# StemsField_motor_V1_0.net
KiCad netlist of a schematic drawn in EAGLE
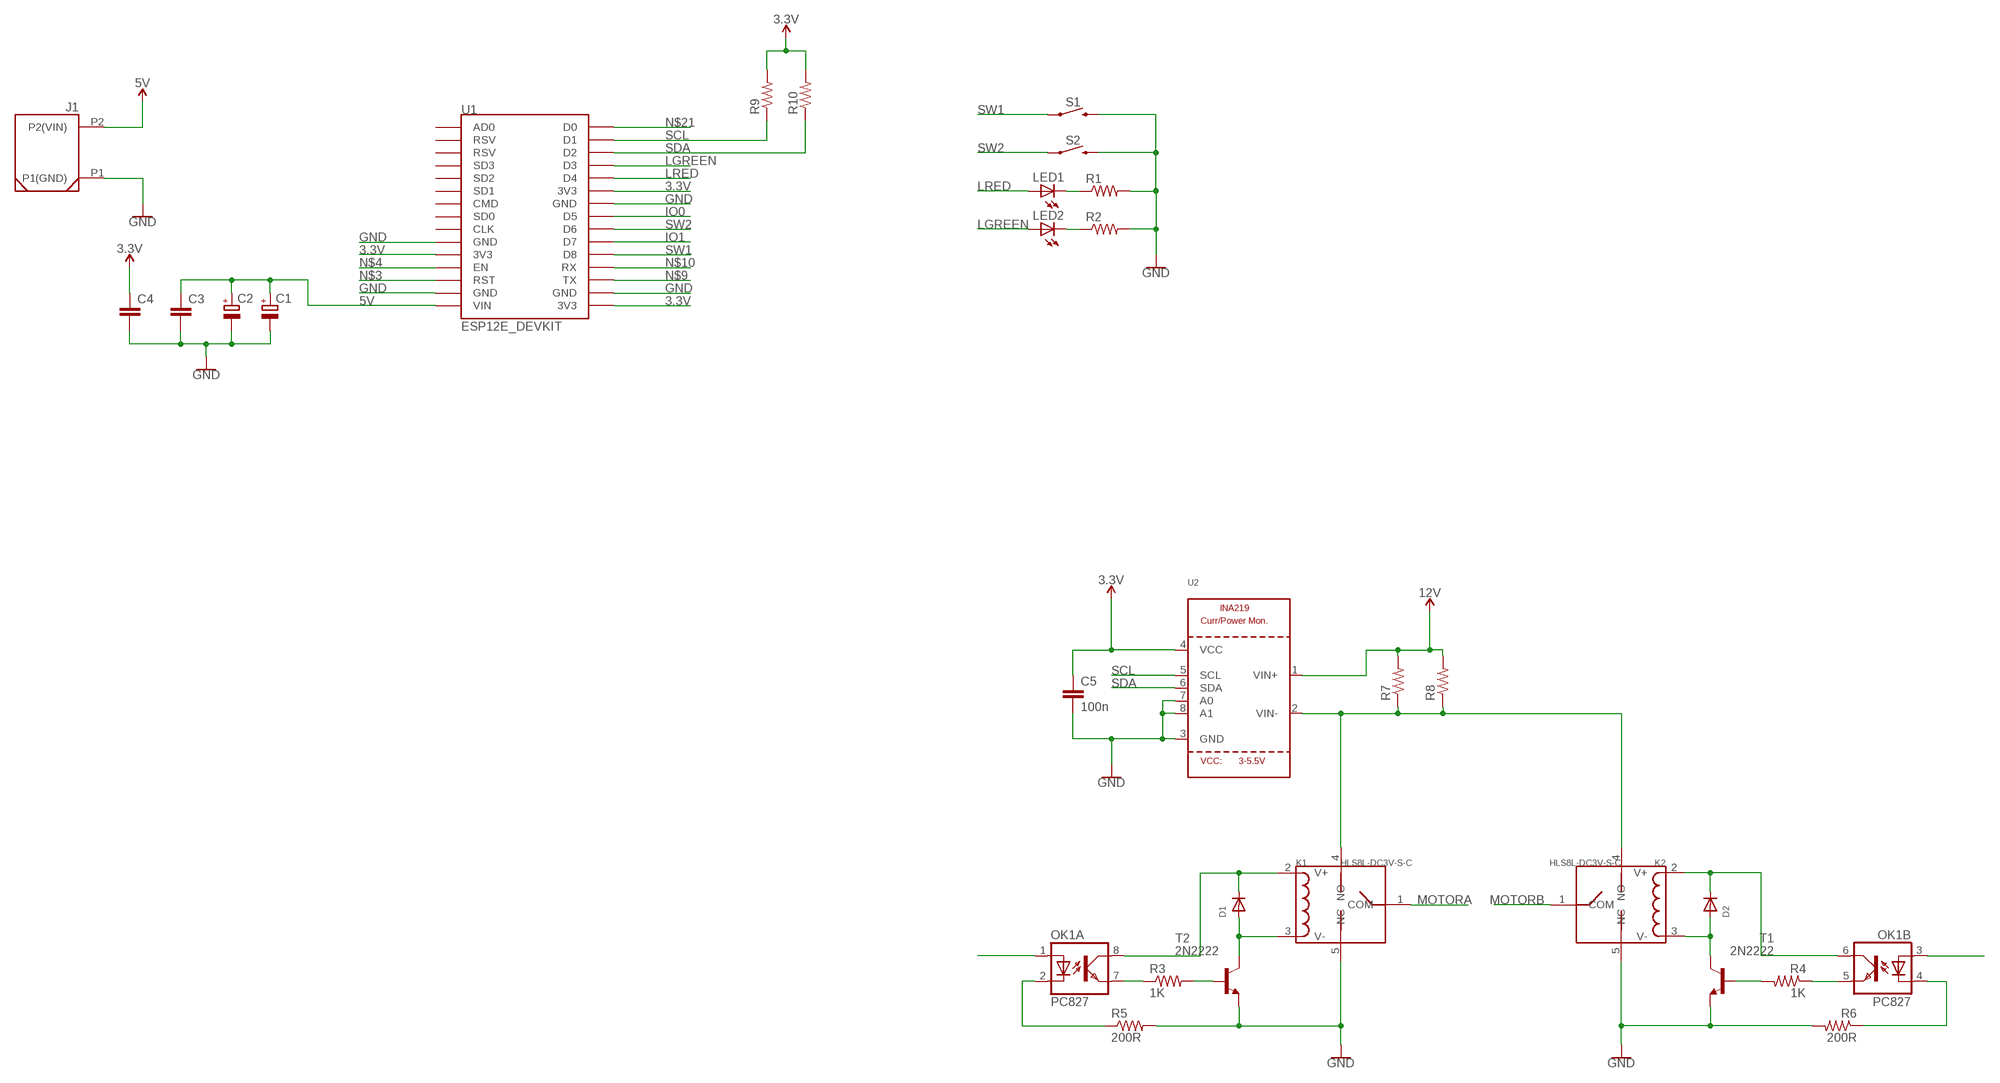
[diagram p0: schematic, sheet 1]

(export (version "E")
  (design (tool "Eeschema 10.0.6"))
  (components
    (comp (ref "C1")
      (value "CPOL-EUE3.5-8")
      (footprint "eagle-import:E3,5-8")
      (libsource (lib "eagle-import") (part "CPOL-EUE3.5-8"))
    )
    (comp (ref "C2")
      (value "CPOL-EUE3.5-8")
      (footprint "eagle-import:E3,5-8")
      (libsource (lib "eagle-import") (part "CPOL-EUE3.5-8"))
    )
    (comp (ref "C3")
      (value "C-EU025-024X044")
      (footprint "eagle-import:C025-024X044")
      (libsource (lib "eagle-import") (part "C-EU025-024X044"))
    )
    (comp (ref "C4")
      (value "C-EU025-024X044")
      (footprint "eagle-import:C025-024X044")
      (libsource (lib "eagle-import") (part "C-EU025-024X044"))
    )
    (comp (ref "C5")
      (value "100n")
      (footprint "eagle-import:C025-024X044")
      (libsource (lib "eagle-import") (part "C-EU025-024X044"))
    )
    (comp (ref "D1")
      (value "DIODEDO-1N4148")
      (footprint "eagle-import:DO-1N4148")
      (libsource (lib "eagle-import") (part "DIODEDO-1N4148"))
    )
    (comp (ref "D2")
      (value "DIODEDO-1N4148")
      (footprint "eagle-import:DO-1N4148")
      (libsource (lib "eagle-import") (part "DIODEDO-1N4148"))
    )
    (comp (ref "J1")
      (value "XT30PWM")
      (footprint "eagle-import:XT30PW-M")
      (libsource (lib "eagle-import") (part "XT30PWM"))
    )
    (comp (ref "K1")
      (value "HLS8L-DC3V-S-C")
      (footprint "eagle-import:REY5-19.0X15.0X15.0MM")
      (libsource (lib "eagle-import") (part "RELAY-HLS8L-DC3V-S-C(5P-19X15MM)"))
    )
    (comp (ref "K2")
      (value "HLS8L-DC3V-S-C")
      (footprint "eagle-import:REY5-19.0X15.0X15.0MM")
      (libsource (lib "eagle-import") (part "RELAY-HLS8L-DC3V-S-C(5P-19X15MM)"))
    )
    (comp (ref "LED1")
      (value "LED3MM")
      (footprint "eagle-import:LED3MM")
      (libsource (lib "eagle-import") (part "LED3MM"))
    )
    (comp (ref "LED2")
      (value "LED3MM")
      (footprint "eagle-import:LED3MM")
      (libsource (lib "eagle-import") (part "LED3MM"))
    )
    (comp (ref "OK1")
      (value "PC827")
      (footprint "eagle-import:DIL08")
      (libsource (lib "eagle-import") (part "PC827"))
    )
    (comp (ref "R1")
      (value "R-US_0204/5")
      (footprint "eagle-import:0204_5")
      (libsource (lib "eagle-import") (part "R-US_0204/5"))
    )
    (comp (ref "R2")
      (value "R-US_0204/5")
      (footprint "eagle-import:0204_5")
      (libsource (lib "eagle-import") (part "R-US_0204/5"))
    )
    (comp (ref "R3")
      (value "1K")
      (footprint "eagle-import:0204_7")
      (libsource (lib "eagle-import") (part "R-US_0204/7"))
    )
    (comp (ref "R4")
      (value "1K")
      (footprint "eagle-import:0204_7")
      (libsource (lib "eagle-import") (part "R-US_0204/7"))
    )
    (comp (ref "R5")
      (value "200R")
      (footprint "eagle-import:0204_7")
      (libsource (lib "eagle-import") (part "R-US_0204/7"))
    )
    (comp (ref "R6")
      (value "200R")
      (footprint "eagle-import:0204_7")
      (libsource (lib "eagle-import") (part "R-US_0204/7"))
    )
    (comp (ref "R7")
      (value "R-US_0204/7")
      (footprint "eagle-import:0204_7")
      (libsource (lib "eagle-import") (part "resistor_348_R-US_0204/7"))
    )
    (comp (ref "R8")
      (value "R-US_R2512")
      (footprint "eagle-import:R2512")
      (libsource (lib "eagle-import") (part "resistor_348_R-US_R2512"))
    )
    (comp (ref "R9")
      (value "R-US_0204/5")
      (footprint "eagle-import:0204_5")
      (libsource (lib "eagle-import") (part "R-US_0204/5"))
    )
    (comp (ref "R10")
      (value "R-US_0204/5")
      (footprint "eagle-import:0204_5")
      (libsource (lib "eagle-import") (part "R-US_0204/5"))
    )
    (comp (ref "S1")
      (value "MOMENTARY-SWITCH-SPST-PTH-6.0MM")
      (footprint "eagle-import:TACTILE_SWITCH_PTH_6.0MM")
      (libsource (lib "eagle-import") (part "MOMENTARY-SWITCH-SPST-PTH-6.0MM"))
    )
    (comp (ref "S2")
      (value "MOMENTARY-SWITCH-SPST-PTH-6.0MM")
      (footprint "eagle-import:TACTILE_SWITCH_PTH_6.0MM")
      (libsource (lib "eagle-import") (part "MOMENTARY-SWITCH-SPST-PTH-6.0MM"))
    )
    (comp (ref "T1")
      (value "2N2222")
      (footprint "eagle-import:TO92-EBC-OVAL")
      (libsource (lib "eagle-import") (part "2N2222"))
    )
    (comp (ref "T2")
      (value "2N2222")
      (footprint "eagle-import:TO92-EBC-OVAL")
      (libsource (lib "eagle-import") (part "2N2222"))
    )
    (comp (ref "U1")
      (value "ESP12E_DEVKIT")
      (footprint "eagle-import:ESP12E_DEVKIT")
      (libsource (lib "eagle-import") (part "ESP12E_DEVKIT"))
    )
    (comp (ref "U2")
      (value "INA219")
      (footprint "eagle-import:SOT23-8")
      (libsource (lib "eagle-import") (part "INA219"))
    )
  )
  (nets
    (net (code "1") (name "/IO0") (class "Default")
      (node (ref "U1") (pin "D5") (pinfunction "D5_D5") (pintype "bidirectional"))
    )
    (net (code "2") (name "/IO1") (class "Default")
      (node (ref "U1") (pin "D7") (pinfunction "D7_D7") (pintype "bidirectional"))
    )
    (net (code "3") (name "/LGREEN") (class "Default")
      (node (ref "LED2") (pin "A") (pinfunction "A_A") (pintype "passive"))
      (node (ref "U1") (pin "D3") (pinfunction "D3_D3") (pintype "bidirectional"))
    )
    (net (code "4") (name "/LRED") (class "Default")
      (node (ref "LED1") (pin "A") (pinfunction "A_A") (pintype "passive"))
      (node (ref "U1") (pin "D4") (pinfunction "D4_D4") (pintype "bidirectional"))
    )
    (net (code "5") (name "/MOTORA") (class "Default")
      (node (ref "K1") (pin "1") (pinfunction "COM_1") (pintype "bidirectional"))
    )
    (net (code "6") (name "/MOTORB") (class "Default")
      (node (ref "K2") (pin "1") (pinfunction "COM_1") (pintype "bidirectional"))
    )
    (net (code "7") (name "/N$3") (class "Default")
      (node (ref "U1") (pin "RST") (pinfunction "RST_RST") (pintype "bidirectional"))
    )
    (net (code "8") (name "/N$4") (class "Default")
      (node (ref "U1") (pin "EN") (pinfunction "EN_EN") (pintype "bidirectional"))
    )
    (net (code "9") (name "/N$9") (class "Default")
      (node (ref "U1") (pin "TX") (pinfunction "TX_TX") (pintype "bidirectional"))
    )
    (net (code "10") (name "/N$10") (class "Default")
      (node (ref "U1") (pin "RX") (pinfunction "RX_RX") (pintype "bidirectional"))
    )
    (net (code "11") (name "/N$21") (class "Default")
      (node (ref "U1") (pin "D0") (pinfunction "D0_D0") (pintype "bidirectional"))
    )
    (net (code "12") (name "/SCL") (class "Default")
      (node (ref "R9") (pin "1") (pinfunction "1_1") (pintype "passive"))
      (node (ref "U1") (pin "D1") (pinfunction "D1_D1") (pintype "bidirectional"))
      (node (ref "U2") (pin "5") (pinfunction "SCL_5") (pintype "bidirectional"))
    )
    (net (code "13") (name "/SDA") (class "Default")
      (node (ref "R10") (pin "1") (pinfunction "1_1") (pintype "passive"))
      (node (ref "U1") (pin "D2") (pinfunction "D2_D2") (pintype "bidirectional"))
      (node (ref "U2") (pin "6") (pinfunction "SDA_6") (pintype "bidirectional"))
    )
    (net (code "14") (name "/SW1") (class "Default")
      (node (ref "S1") (pin "1") (pinfunction "1_1") (pintype "passive"))
      (node (ref "U1") (pin "D8") (pinfunction "D8_D8") (pintype "bidirectional"))
    )
    (net (code "15") (name "/SW2") (class "Default")
      (node (ref "S2") (pin "1") (pinfunction "1_1") (pintype "passive"))
      (node (ref "U1") (pin "D6") (pinfunction "D6_D6") (pintype "bidirectional"))
    )
    (net (code "16") (name "3.3V") (class "Default")
      (node (ref "C4") (pin "1") (pinfunction "1_1") (pintype "passive"))
      (node (ref "C5") (pin "1") (pinfunction "1_1") (pintype "passive"))
      (node (ref "R10") (pin "2") (pinfunction "2_2") (pintype "passive"))
      (node (ref "R9") (pin "2") (pinfunction "2_2") (pintype "passive"))
      (node (ref "U1") (pin "3V3@0") (pinfunction "3V3_3V3@0") (pintype "bidirectional"))
      (node (ref "U1") (pin "3V3@1") (pinfunction "3V3_3V3@1") (pintype "bidirectional"))
      (node (ref "U1") (pin "3V3@2") (pinfunction "3V3_3V3@2") (pintype "bidirectional"))
      (node (ref "U2") (pin "4") (pinfunction "VCC_4") (pintype "bidirectional"))
    )
    (net (code "17") (name "5V") (class "Default")
      (node (ref "C1") (pin "+") (pinfunction "+_+") (pintype "passive"))
      (node (ref "C2") (pin "+") (pinfunction "+_+") (pintype "passive"))
      (node (ref "C3") (pin "1") (pinfunction "1_1") (pintype "passive"))
      (node (ref "J1") (pin "P2") (pinfunction "P2(VIN)_P2") (pintype "bidirectional"))
      (node (ref "U1") (pin "VIN") (pinfunction "VIN_VIN") (pintype "bidirectional"))
    )
    (net (code "18") (name "12V") (class "Default")
      (node (ref "R7") (pin "2") (pinfunction "2_2") (pintype "passive"))
      (node (ref "R8") (pin "2") (pinfunction "2_2") (pintype "passive"))
      (node (ref "U2") (pin "1") (pinfunction "VIN+_1") (pintype "bidirectional"))
    )
    (net (code "19") (name "GND") (class "Default")
      (node (ref "C1") (pin "-") (pinfunction "-_-") (pintype "passive"))
      (node (ref "C2") (pin "-") (pinfunction "-_-") (pintype "passive"))
      (node (ref "C3") (pin "2") (pinfunction "2_2") (pintype "passive"))
      (node (ref "C4") (pin "2") (pinfunction "2_2") (pintype "passive"))
      (node (ref "C5") (pin "2") (pinfunction "2_2") (pintype "passive"))
      (node (ref "J1") (pin "P1") (pinfunction "P1(GND)_P1") (pintype "bidirectional"))
      (node (ref "K1") (pin "5") (pinfunction "NC_5") (pintype "bidirectional"))
      (node (ref "K2") (pin "5") (pinfunction "NC_5") (pintype "bidirectional"))
      (node (ref "R1") (pin "2") (pinfunction "2_2") (pintype "passive"))
      (node (ref "R2") (pin "2") (pinfunction "2_2") (pintype "passive"))
      (node (ref "R5") (pin "2") (pinfunction "2_2") (pintype "passive"))
      (node (ref "R6") (pin "2") (pinfunction "2_2") (pintype "passive"))
      (node (ref "S1") (pin "3") (pinfunction "2_3") (pintype "passive"))
      (node (ref "S2") (pin "3") (pinfunction "2_3") (pintype "passive"))
      (node (ref "T1") (pin "E") (pinfunction "E_E") (pintype "passive"))
      (node (ref "T2") (pin "E") (pinfunction "E_E") (pintype "passive"))
      (node (ref "U1") (pin "GND@0") (pinfunction "GND_GND@0") (pintype "bidirectional"))
      (node (ref "U1") (pin "GND@1") (pinfunction "GND_GND@1") (pintype "bidirectional"))
      (node (ref "U1") (pin "GND@2") (pinfunction "GND_GND@2") (pintype "bidirectional"))
      (node (ref "U1") (pin "GND@3") (pinfunction "GND_GND@3") (pintype "bidirectional"))
      (node (ref "U2") (pin "3") (pinfunction "GND_3") (pintype "bidirectional"))
      (node (ref "U2") (pin "7") (pinfunction "A0_7") (pintype "bidirectional"))
      (node (ref "U2") (pin "8") (pinfunction "A1_8") (pintype "bidirectional"))
    )
    (net (code "20") (name "Net-(K1-NO)") (class "Default")
      (node (ref "K1") (pin "4") (pinfunction "NO_4") (pintype "bidirectional"))
      (node (ref "K2") (pin "4") (pinfunction "NO_4") (pintype "bidirectional"))
      (node (ref "R7") (pin "1") (pinfunction "1_1") (pintype "passive"))
      (node (ref "R8") (pin "1") (pinfunction "1_1") (pintype "passive"))
      (node (ref "U2") (pin "2") (pinfunction "VIN-_2") (pintype "bidirectional"))
    )
    (net (code "21") (name "Net-(K1-V+)") (class "Default")
      (node (ref "D1") (pin "C") (pinfunction "C_C") (pintype "passive"))
      (node (ref "K1") (pin "2") (pinfunction "V+_2") (pintype "bidirectional"))
      (node (ref "OK1") (pin "8") (pinfunction "COL_8") (pintype "passive"))
    )
    (net (code "22") (name "Net-(K1-V-)") (class "Default")
      (node (ref "D1") (pin "A") (pinfunction "A_A") (pintype "passive"))
      (node (ref "K1") (pin "3") (pinfunction "V-_3") (pintype "bidirectional"))
      (node (ref "T2") (pin "C") (pinfunction "C_C") (pintype "passive"))
    )
    (net (code "23") (name "Net-(K2-V+)") (class "Default")
      (node (ref "D2") (pin "C") (pinfunction "C_C") (pintype "passive"))
      (node (ref "K2") (pin "2") (pinfunction "V+_2") (pintype "bidirectional"))
      (node (ref "OK1") (pin "6") (pinfunction "COL_6") (pintype "passive"))
    )
    (net (code "24") (name "Net-(K2-V-)") (class "Default")
      (node (ref "D2") (pin "A") (pinfunction "A_A") (pintype "passive"))
      (node (ref "K2") (pin "3") (pinfunction "V-_3") (pintype "bidirectional"))
      (node (ref "T1") (pin "C") (pinfunction "C_C") (pintype "passive"))
    )
    (net (code "25") (name "Net-(LED1-C)") (class "Default")
      (node (ref "LED1") (pin "K") (pinfunction "C_K") (pintype "passive"))
      (node (ref "R1") (pin "1") (pinfunction "1_1") (pintype "passive"))
    )
    (net (code "26") (name "Net-(LED2-C)") (class "Default")
      (node (ref "LED2") (pin "K") (pinfunction "C_K") (pintype "passive"))
      (node (ref "R2") (pin "1") (pinfunction "1_1") (pintype "passive"))
    )
    (net (code "27") (name "Net-(OK1A-C)") (class "Default")
      (node (ref "OK1") (pin "2") (pinfunction "C_2") (pintype "passive"))
      (node (ref "R5") (pin "1") (pinfunction "1_1") (pintype "passive"))
    )
    (net (code "28") (name "Net-(OK1A-EMIT)") (class "Default")
      (node (ref "OK1") (pin "7") (pinfunction "EMIT_7") (pintype "passive"))
      (node (ref "R3") (pin "1") (pinfunction "1_1") (pintype "passive"))
    )
    (net (code "29") (name "Net-(OK1B-C)") (class "Default")
      (node (ref "OK1") (pin "4") (pinfunction "C_4") (pintype "passive"))
      (node (ref "R6") (pin "1") (pinfunction "1_1") (pintype "passive"))
    )
    (net (code "30") (name "Net-(OK1B-EMIT)") (class "Default")
      (node (ref "OK1") (pin "5") (pinfunction "EMIT_5") (pintype "passive"))
      (node (ref "R4") (pin "1") (pinfunction "1_1") (pintype "passive"))
    )
    (net (code "31") (name "Net-(R3-Pad2)") (class "Default")
      (node (ref "R3") (pin "2") (pinfunction "2_2") (pintype "passive"))
      (node (ref "T2") (pin "B") (pinfunction "B_B") (pintype "passive"))
    )
    (net (code "32") (name "Net-(R4-Pad2)") (class "Default")
      (node (ref "R4") (pin "2") (pinfunction "2_2") (pintype "passive"))
      (node (ref "T1") (pin "B") (pinfunction "B_B") (pintype "passive"))
    )
    (net (code "33") (name "unconnected-(OK1A-A-Pad1)") (class "Default")
      (node (ref "OK1") (pin "1") (pinfunction "A_1") (pintype "passive"))
    )
    (net (code "34") (name "unconnected-(OK1B-A-Pad3)") (class "Default")
      (node (ref "OK1") (pin "3") (pinfunction "A_3") (pintype "passive"))
    )
    (net (code "35") (name "unconnected-(U1-PadAD0)") (class "Default")
      (node (ref "U1") (pin "AD0") (pinfunction "AD0_AD0") (pintype "bidirectional"))
    )
    (net (code "36") (name "unconnected-(U1-PadCLK)") (class "Default")
      (node (ref "U1") (pin "CLK") (pinfunction "CLK_CLK") (pintype "bidirectional"))
    )
    (net (code "37") (name "unconnected-(U1-PadCMD)") (class "Default")
      (node (ref "U1") (pin "CMD") (pinfunction "CMD_CMD") (pintype "bidirectional"))
    )
    (net (code "38") (name "unconnected-(U1-PadSD0)") (class "Default")
      (node (ref "U1") (pin "SD0") (pinfunction "SD0_SD0") (pintype "bidirectional"))
    )
    (net (code "39") (name "unconnected-(U1-PadSD1)") (class "Default")
      (node (ref "U1") (pin "SD1") (pinfunction "SD1_SD1") (pintype "bidirectional"))
    )
    (net (code "40") (name "unconnected-(U1-PadSD2)") (class "Default")
      (node (ref "U1") (pin "SD2") (pinfunction "SD2_SD2") (pintype "bidirectional"))
    )
    (net (code "41") (name "unconnected-(U1-PadSD3)") (class "Default")
      (node (ref "U1") (pin "SD3") (pinfunction "SD3_SD3") (pintype "bidirectional"))
    )
    (net (code "42") (name "unconnected-(U1-RSV-PadRSV@0)") (class "Default")
      (node (ref "U1") (pin "RSV@0") (pinfunction "RSV_RSV@0") (pintype "bidirectional"))
    )
    (net (code "43") (name "unconnected-(U1-RSV-PadRSV@1)") (class "Default")
      (node (ref "U1") (pin "RSV@1") (pinfunction "RSV_RSV@1") (pintype "bidirectional"))
    )
  )
)
